# ProPrj__PCB__2026-04-20.net
KiCad netlist of a schematic drawn in EasyEDA Pro
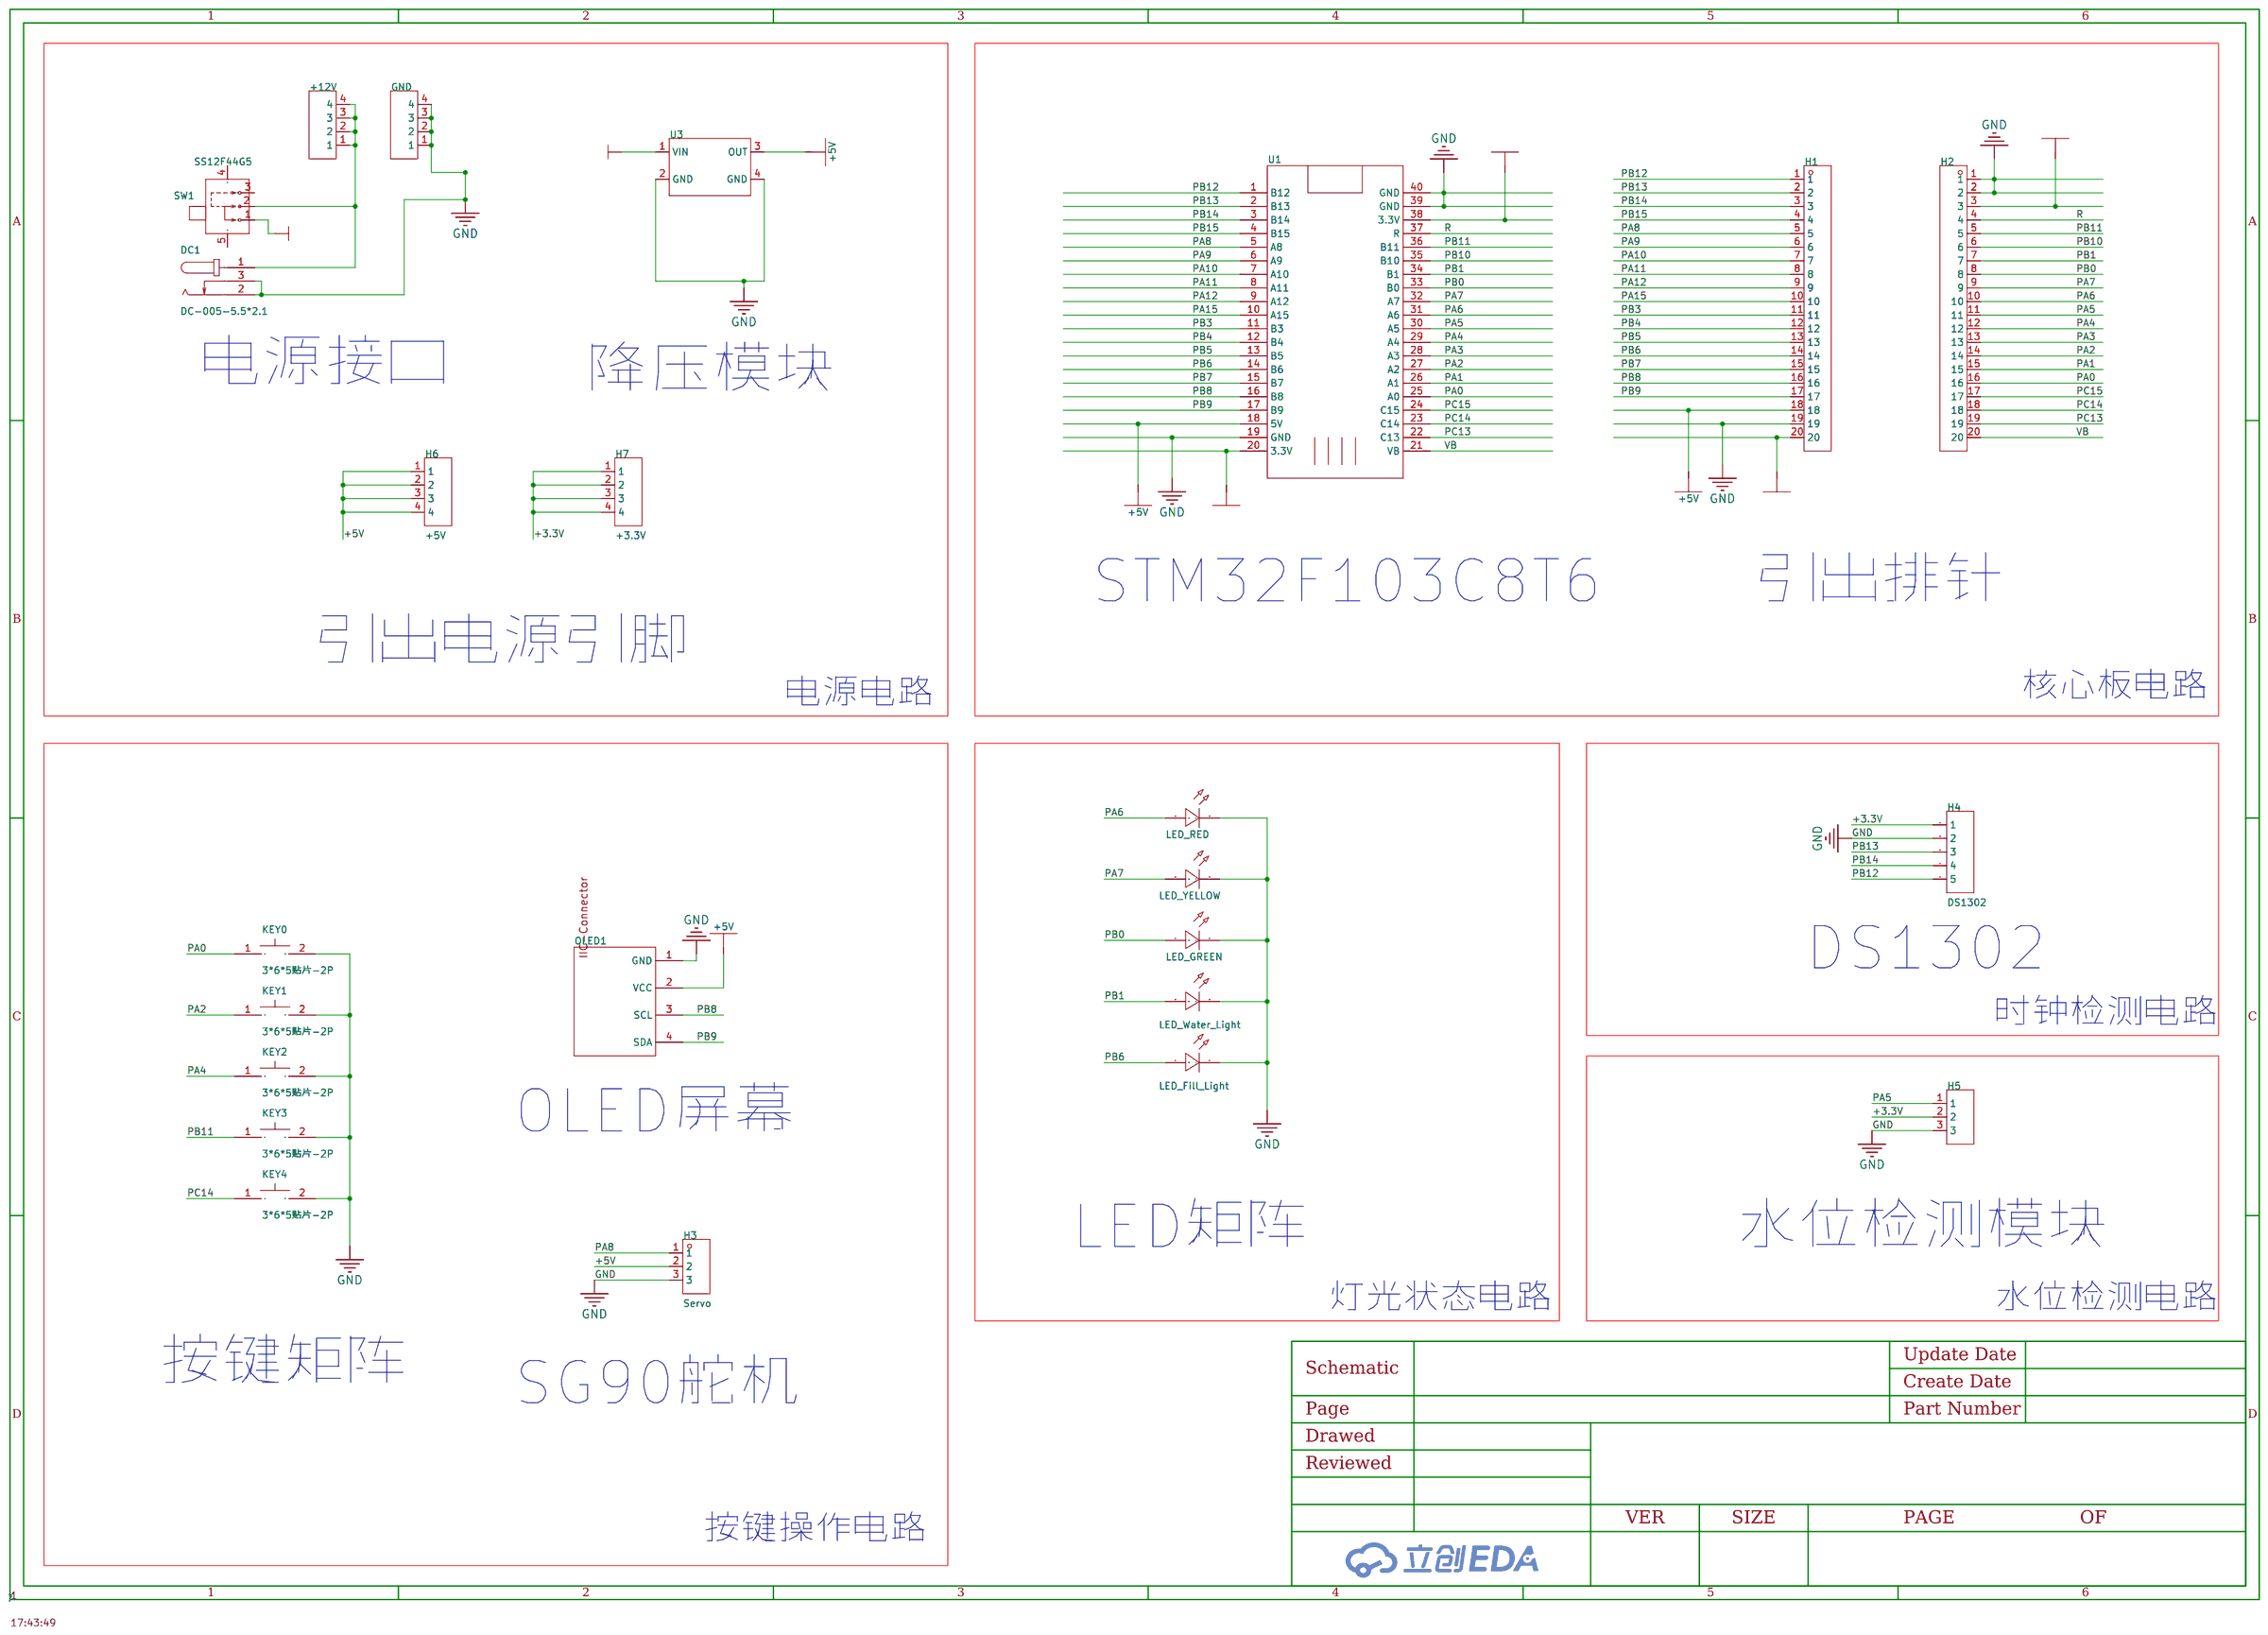
[diagram p0: schematic sheet]

(export (version "E")
  (design (tool "Eeschema 10.0.6"))
  (components
    (comp (ref "+12V")
      (value "~")
      (footprint "easyedapro:HDR-TH_4P-P2.54-V-M")
      (libsource (lib "easyedapro") (part "PZ254V-11-04P"))
    )
    (comp (ref "DC1")
      (value "DC-005-5.5*2.1")
      (footprint "easyedapro:DC-IN-TH_DC-005-2")
      (libsource (lib "easyedapro") (part "DC-005-5.5*2.1"))
    )
    (comp (ref "GND")
      (value "~")
      (footprint "easyedapro:HDR-TH_4P-P2.54-V-M")
      (libsource (lib "easyedapro") (part "PZ254V-11-04P"))
    )
    (comp (ref "H1")
      (value "~")
      (footprint "easyedapro:HDR-TH_20P-P2.54-V-M-1")
      (libsource (lib "easyedapro") (part "HDR_2.54-1x20P"))
    )
    (comp (ref "H2")
      (value "~")
      (footprint "easyedapro:HDR-TH_20P-P2.54-V-M-1")
      (libsource (lib "easyedapro") (part "HDR_2.54-1x20P"))
    )
    (comp (ref "H3")
      (value "Servo")
      (footprint "easyedapro:HDR-TH_3P-P2.54-V-M")
      (libsource (lib "easyedapro") (part "HDR-M_2.54_1x3P"))
    )
    (comp (ref "H4")
      (value "DS1302")
      (footprint "easyedapro:HDR-TH_5P-P2.54-V-F")
      (libsource (lib "easyedapro") (part "Header-Female-2.54_1x5"))
    )
    (comp (ref "H5")
      (value "~")
      (footprint "easyedapro:HDR-TH_3P-P2.54-V-F")
      (libsource (lib "easyedapro") (part "PM254V-11-03-H85"))
    )
    (comp (ref "H6")
      (value "+5V")
      (footprint "easyedapro:HDR-TH_4P-P2.54-V-M")
      (libsource (lib "easyedapro") (part "PZ254V-11-04P"))
    )
    (comp (ref "H7")
      (value "+3.3V")
      (footprint "easyedapro:HDR-TH_4P-P2.54-V-M")
      (libsource (lib "easyedapro") (part "PZ254V-11-04P"))
    )
    (comp (ref "KEY0")
      (value "3*6*5贴片-2P")
      (footprint "easyedapro:SW-SMD_L6.0-W3.5-LS8.0")
      (libsource (lib "easyedapro") (part "3*6*5贴片-2P"))
    )
    (comp (ref "KEY1")
      (value "3*6*5贴片-2P")
      (footprint "easyedapro:SW-SMD_L6.0-W3.5-LS8.0")
      (libsource (lib "easyedapro") (part "3*6*5贴片-2P"))
    )
    (comp (ref "KEY2")
      (value "3*6*5贴片-2P")
      (footprint "easyedapro:SW-SMD_L6.0-W3.5-LS8.0")
      (libsource (lib "easyedapro") (part "3*6*5贴片-2P"))
    )
    (comp (ref "KEY3")
      (value "3*6*5贴片-2P")
      (footprint "easyedapro:SW-SMD_L6.0-W3.5-LS8.0")
      (libsource (lib "easyedapro") (part "3*6*5贴片-2P"))
    )
    (comp (ref "KEY4")
      (value "3*6*5贴片-2P")
      (footprint "easyedapro:SW-SMD_L6.0-W3.5-LS8.0")
      (libsource (lib "easyedapro") (part "3*6*5贴片-2P"))
    )
    (comp (ref "LED_Fill_Light")
      (value "~")
      (footprint "easyedapro:LED_TH-_5mm")
      (libsource (lib "easyedapro") (part "LED_TH-B"))
    )
    (comp (ref "LED_GREEN")
      (value "~")
      (footprint "easyedapro:LED_TH-_5mm")
      (libsource (lib "easyedapro") (part "LED_TH-G"))
    )
    (comp (ref "LED_RED")
      (value "~")
      (footprint "easyedapro:LED_TH-_5mm")
      (libsource (lib "easyedapro") (part "LED_TH-R"))
    )
    (comp (ref "LED_Water_Light")
      (value "~")
      (footprint "easyedapro:LED_TH-_5mm")
      (libsource (lib "easyedapro") (part "LED_TH-B"))
    )
    (comp (ref "LED_YELLOW")
      (value "~")
      (footprint "easyedapro:LED_TH-_5mm")
      (libsource (lib "easyedapro") (part "LED_TH-B"))
    )
    (comp (ref "OLED1")
      (value "~")
      (fields (field (name "Manufacturer Part") "0.96OLED_4P_MODULE_JX"))
      (libsource (lib "easyedapro") (part "0.96OLED_4P_MODULE_JX"))
    )
    (comp (ref "SW1")
      (value "SS12F44G5")
      (footprint "easyedapro:SW-TH_SHOU-HAN_SS12F44G4")
      (description "拨动开关 立式直脚插件 二档 柄高5mm")
      (fields (field (name "Manufacturer") "HanElectricity(瀚源)"))
      (libsource (lib "easyedapro") (part "SS12F44G5"))
    )
    (comp (ref "U1") (value "~") (libsource (lib "easyedapro") (part "STM32F103C8T6核心板")))
    (comp (ref "U3")
      (value "~")
      (footprint "easyedapro:MP1584模块")
      (libsource (lib "easyedapro") (part "MP1584模块"))
    )
  )
  (nets
    (net (code "1") (name "+3.3V") (class "Default")
      (node (ref "H1") (pin "20") (pinfunction "20_20") (pintype "input"))
      (node (ref "H2") (pin "3") (pinfunction "3_3") (pintype "input"))
      (node (ref "H4") (pin "1") (pinfunction "1_1") (pintype "input"))
      (node (ref "H5") (pin "2") (pinfunction "2_2") (pintype "unspecified"))
      (node (ref "H7") (pin "1") (pinfunction "1_1") (pintype "unspecified"))
      (node (ref "H7") (pin "2") (pinfunction "2_2") (pintype "unspecified"))
      (node (ref "H7") (pin "3") (pinfunction "3_3") (pintype "unspecified"))
      (node (ref "H7") (pin "4") (pinfunction "4_4") (pintype "unspecified"))
      (node (ref "U1") (pin "20") (pinfunction "3.3V_20") (pintype "unspecified"))
      (node (ref "U1") (pin "38") (pinfunction "3.3V_38") (pintype "unspecified"))
    )
    (net (code "2") (name "+5V") (class "Default")
      (node (ref "H1") (pin "18") (pinfunction "18_18") (pintype "input"))
      (node (ref "H3") (pin "2") (pinfunction "2_2") (pintype "input"))
      (node (ref "H6") (pin "1") (pinfunction "1_1") (pintype "unspecified"))
      (node (ref "H6") (pin "2") (pinfunction "2_2") (pintype "unspecified"))
      (node (ref "H6") (pin "3") (pinfunction "3_3") (pintype "unspecified"))
      (node (ref "H6") (pin "4") (pinfunction "4_4") (pintype "unspecified"))
      (node (ref "OLED1") (pin "2") (pinfunction "VCC_2") (pintype "input"))
      (node (ref "U1") (pin "18") (pinfunction "5V_18") (pintype "unspecified"))
      (node (ref "U3") (pin "3") (pinfunction "OUT_3") (pintype "unspecified"))
    )
    (net (code "3") (name "+12V") (class "Default")
      (node (ref "SW1") (pin "1") (pinfunction "1_1") (pintype "unspecified"))
      (node (ref "U3") (pin "1") (pinfunction "VIN_1") (pintype "unspecified"))
    )
    (net (code "4") (name "/PA0") (class "Default")
      (node (ref "H2") (pin "16") (pinfunction "16_16") (pintype "input"))
      (node (ref "KEY0") (pin "1") (pinfunction "1_1") (pintype "unspecified"))
      (node (ref "U1") (pin "25") (pinfunction "A0_25") (pintype "unspecified"))
    )
    (net (code "5") (name "/PA1") (class "Default")
      (node (ref "H2") (pin "15") (pinfunction "15_15") (pintype "input"))
      (node (ref "U1") (pin "26") (pinfunction "A1_26") (pintype "unspecified"))
    )
    (net (code "6") (name "/PA2") (class "Default")
      (node (ref "H2") (pin "14") (pinfunction "14_14") (pintype "input"))
      (node (ref "KEY1") (pin "1") (pinfunction "1_1") (pintype "unspecified"))
      (node (ref "U1") (pin "27") (pinfunction "A2_27") (pintype "unspecified"))
    )
    (net (code "7") (name "/PA3") (class "Default")
      (node (ref "H2") (pin "13") (pinfunction "13_13") (pintype "input"))
      (node (ref "U1") (pin "28") (pinfunction "A3_28") (pintype "unspecified"))
    )
    (net (code "8") (name "/PA4") (class "Default")
      (node (ref "H2") (pin "12") (pinfunction "12_12") (pintype "input"))
      (node (ref "KEY2") (pin "1") (pinfunction "1_1") (pintype "unspecified"))
      (node (ref "U1") (pin "29") (pinfunction "A4_29") (pintype "unspecified"))
    )
    (net (code "9") (name "/PA5") (class "Default")
      (node (ref "H2") (pin "11") (pinfunction "11_11") (pintype "input"))
      (node (ref "H5") (pin "1") (pinfunction "1_1") (pintype "unspecified"))
      (node (ref "U1") (pin "30") (pinfunction "A5_30") (pintype "unspecified"))
    )
    (net (code "10") (name "/PA6") (class "Default")
      (node (ref "H2") (pin "10") (pinfunction "10_10") (pintype "input"))
      (node (ref "LED_RED") (pin "1") (pinfunction "C_1") (pintype "input"))
      (node (ref "U1") (pin "31") (pinfunction "A6_31") (pintype "unspecified"))
    )
    (net (code "11") (name "/PA7") (class "Default")
      (node (ref "H2") (pin "9") (pinfunction "9_9") (pintype "input"))
      (node (ref "LED_YELLOW") (pin "1") (pinfunction "C_1") (pintype "input"))
      (node (ref "U1") (pin "32") (pinfunction "A7_32") (pintype "unspecified"))
    )
    (net (code "12") (name "/PA8") (class "Default")
      (node (ref "H1") (pin "5") (pinfunction "5_5") (pintype "input"))
      (node (ref "H3") (pin "1") (pinfunction "1_1") (pintype "input"))
      (node (ref "U1") (pin "5") (pinfunction "A8_5") (pintype "unspecified"))
    )
    (net (code "13") (name "/PA9") (class "Default")
      (node (ref "H1") (pin "6") (pinfunction "6_6") (pintype "input"))
      (node (ref "U1") (pin "6") (pinfunction "A9_6") (pintype "unspecified"))
    )
    (net (code "14") (name "/PA10") (class "Default")
      (node (ref "H1") (pin "7") (pinfunction "7_7") (pintype "input"))
      (node (ref "U1") (pin "7") (pinfunction "A10_7") (pintype "unspecified"))
    )
    (net (code "15") (name "/PA11") (class "Default")
      (node (ref "H1") (pin "8") (pinfunction "8_8") (pintype "input"))
      (node (ref "U1") (pin "8") (pinfunction "A11_8") (pintype "unspecified"))
    )
    (net (code "16") (name "/PA12") (class "Default")
      (node (ref "H1") (pin "9") (pinfunction "9_9") (pintype "input"))
      (node (ref "U1") (pin "9") (pinfunction "A12_9") (pintype "unspecified"))
    )
    (net (code "17") (name "/PA15") (class "Default")
      (node (ref "H1") (pin "10") (pinfunction "10_10") (pintype "input"))
      (node (ref "U1") (pin "10") (pinfunction "A15_10") (pintype "unspecified"))
    )
    (net (code "18") (name "/PB0") (class "Default")
      (node (ref "H2") (pin "8") (pinfunction "8_8") (pintype "input"))
      (node (ref "LED_GREEN") (pin "1") (pinfunction "C_1") (pintype "input"))
      (node (ref "U1") (pin "33") (pinfunction "B0_33") (pintype "unspecified"))
    )
    (net (code "19") (name "/PB1") (class "Default")
      (node (ref "H2") (pin "7") (pinfunction "7_7") (pintype "input"))
      (node (ref "LED_Water_Light") (pin "1") (pinfunction "C_1") (pintype "input"))
      (node (ref "U1") (pin "34") (pinfunction "B1_34") (pintype "unspecified"))
    )
    (net (code "20") (name "/PB3") (class "Default")
      (node (ref "H1") (pin "11") (pinfunction "11_11") (pintype "input"))
      (node (ref "U1") (pin "11") (pinfunction "B3_11") (pintype "unspecified"))
    )
    (net (code "21") (name "/PB4") (class "Default")
      (node (ref "H1") (pin "12") (pinfunction "12_12") (pintype "input"))
      (node (ref "U1") (pin "12") (pinfunction "B4_12") (pintype "unspecified"))
    )
    (net (code "22") (name "/PB5") (class "Default")
      (node (ref "H1") (pin "13") (pinfunction "13_13") (pintype "input"))
      (node (ref "U1") (pin "13") (pinfunction "B5_13") (pintype "unspecified"))
    )
    (net (code "23") (name "/PB6") (class "Default")
      (node (ref "H1") (pin "14") (pinfunction "14_14") (pintype "input"))
      (node (ref "LED_Fill_Light") (pin "1") (pinfunction "C_1") (pintype "input"))
      (node (ref "U1") (pin "14") (pinfunction "B6_14") (pintype "unspecified"))
    )
    (net (code "24") (name "/PB7") (class "Default")
      (node (ref "H1") (pin "15") (pinfunction "15_15") (pintype "input"))
      (node (ref "U1") (pin "15") (pinfunction "B7_15") (pintype "unspecified"))
    )
    (net (code "25") (name "/PB8") (class "Default")
      (node (ref "H1") (pin "16") (pinfunction "16_16") (pintype "input"))
      (node (ref "OLED1") (pin "3") (pinfunction "SCL_3") (pintype "input"))
      (node (ref "U1") (pin "16") (pinfunction "B8_16") (pintype "unspecified"))
    )
    (net (code "26") (name "/PB9") (class "Default")
      (node (ref "H1") (pin "17") (pinfunction "17_17") (pintype "input"))
      (node (ref "OLED1") (pin "4") (pinfunction "SDA_4") (pintype "input"))
      (node (ref "U1") (pin "17") (pinfunction "B9_17") (pintype "unspecified"))
    )
    (net (code "27") (name "/PB10") (class "Default")
      (node (ref "H2") (pin "6") (pinfunction "6_6") (pintype "input"))
      (node (ref "U1") (pin "35") (pinfunction "B10_35") (pintype "unspecified"))
    )
    (net (code "28") (name "/PB11") (class "Default")
      (node (ref "H2") (pin "5") (pinfunction "5_5") (pintype "input"))
      (node (ref "KEY3") (pin "1") (pinfunction "1_1") (pintype "unspecified"))
      (node (ref "U1") (pin "36") (pinfunction "B11_36") (pintype "unspecified"))
    )
    (net (code "29") (name "/PB12") (class "Default")
      (node (ref "H1") (pin "1") (pinfunction "1_1") (pintype "input"))
      (node (ref "H4") (pin "5") (pinfunction "5_5") (pintype "input"))
      (node (ref "U1") (pin "1") (pinfunction "B12_1") (pintype "unspecified"))
    )
    (net (code "30") (name "/PB13") (class "Default")
      (node (ref "H1") (pin "2") (pinfunction "2_2") (pintype "input"))
      (node (ref "H4") (pin "3") (pinfunction "3_3") (pintype "input"))
      (node (ref "U1") (pin "2") (pinfunction "B13_2") (pintype "unspecified"))
    )
    (net (code "31") (name "/PB14") (class "Default")
      (node (ref "H1") (pin "3") (pinfunction "3_3") (pintype "input"))
      (node (ref "H4") (pin "4") (pinfunction "4_4") (pintype "input"))
      (node (ref "U1") (pin "3") (pinfunction "B14_3") (pintype "unspecified"))
    )
    (net (code "32") (name "/PB15") (class "Default")
      (node (ref "H1") (pin "4") (pinfunction "4_4") (pintype "input"))
      (node (ref "U1") (pin "4") (pinfunction "B15_4") (pintype "unspecified"))
    )
    (net (code "33") (name "/PC13") (class "Default")
      (node (ref "H2") (pin "19") (pinfunction "19_19") (pintype "input"))
      (node (ref "U1") (pin "22") (pinfunction "C13_22") (pintype "unspecified"))
    )
    (net (code "34") (name "/PC14") (class "Default")
      (node (ref "H2") (pin "18") (pinfunction "18_18") (pintype "input"))
      (node (ref "KEY4") (pin "1") (pinfunction "1_1") (pintype "unspecified"))
      (node (ref "U1") (pin "23") (pinfunction "C14_23") (pintype "unspecified"))
    )
    (net (code "35") (name "/PC15") (class "Default")
      (node (ref "H2") (pin "17") (pinfunction "17_17") (pintype "input"))
      (node (ref "U1") (pin "24") (pinfunction "C15_24") (pintype "unspecified"))
    )
    (net (code "36") (name "/R") (class "Default")
      (node (ref "H2") (pin "4") (pinfunction "4_4") (pintype "input"))
      (node (ref "U1") (pin "37") (pinfunction "R_37") (pintype "unspecified"))
    )
    (net (code "37") (name "/VB") (class "Default")
      (node (ref "H2") (pin "20") (pinfunction "20_20") (pintype "input"))
      (node (ref "U1") (pin "21") (pinfunction "VB_21") (pintype "unspecified"))
    )
    (net (code "38") (name "GND") (class "Default")
      (node (ref "DC1") (pin "2") (pinfunction "2_2") (pintype "unspecified"))
      (node (ref "DC1") (pin "3") (pinfunction "3_3") (pintype "unspecified"))
      (node (ref "GND") (pin "1") (pinfunction "1_1") (pintype "unspecified"))
      (node (ref "GND") (pin "2") (pinfunction "2_2") (pintype "unspecified"))
      (node (ref "GND") (pin "3") (pinfunction "3_3") (pintype "unspecified"))
      (node (ref "GND") (pin "4") (pinfunction "4_4") (pintype "unspecified"))
      (node (ref "H1") (pin "19") (pinfunction "19_19") (pintype "input"))
      (node (ref "H2") (pin "1") (pinfunction "1_1") (pintype "input"))
      (node (ref "H2") (pin "2") (pinfunction "2_2") (pintype "input"))
      (node (ref "H3") (pin "3") (pinfunction "3_3") (pintype "input"))
      (node (ref "H4") (pin "2") (pinfunction "2_2") (pintype "input"))
      (node (ref "H5") (pin "3") (pinfunction "3_3") (pintype "unspecified"))
      (node (ref "KEY0") (pin "2") (pinfunction "2_2") (pintype "unspecified"))
      (node (ref "KEY1") (pin "2") (pinfunction "2_2") (pintype "unspecified"))
      (node (ref "KEY2") (pin "2") (pinfunction "2_2") (pintype "unspecified"))
      (node (ref "KEY3") (pin "2") (pinfunction "2_2") (pintype "unspecified"))
      (node (ref "KEY4") (pin "2") (pinfunction "2_2") (pintype "unspecified"))
      (node (ref "LED_Fill_Light") (pin "2") (pinfunction "A_2") (pintype "input"))
      (node (ref "LED_GREEN") (pin "2") (pinfunction "A_2") (pintype "input"))
      (node (ref "LED_RED") (pin "2") (pinfunction "A_2") (pintype "input"))
      (node (ref "LED_Water_Light") (pin "2") (pinfunction "A_2") (pintype "input"))
      (node (ref "LED_YELLOW") (pin "2") (pinfunction "A_2") (pintype "input"))
      (node (ref "OLED1") (pin "1") (pinfunction "GND_1") (pintype "input"))
      (node (ref "U1") (pin "19") (pinfunction "GND_19") (pintype "unspecified"))
      (node (ref "U1") (pin "39") (pinfunction "GND_39") (pintype "unspecified"))
      (node (ref "U1") (pin "40") (pinfunction "GND_40") (pintype "unspecified"))
      (node (ref "U3") (pin "2") (pinfunction "GND_2") (pintype "unspecified"))
      (node (ref "U3") (pin "4") (pinfunction "GND_4") (pintype "unspecified"))
    )
    (net (code "39") (name "Net-(+12V-Pad1)") (class "Default")
      (node (ref "+12V") (pin "1") (pinfunction "1_1") (pintype "unspecified"))
      (node (ref "+12V") (pin "2") (pinfunction "2_2") (pintype "unspecified"))
      (node (ref "+12V") (pin "3") (pinfunction "3_3") (pintype "unspecified"))
      (node (ref "+12V") (pin "4") (pinfunction "4_4") (pintype "unspecified"))
      (node (ref "DC1") (pin "1") (pinfunction "1_1") (pintype "unspecified"))
      (node (ref "SW1") (pin "2") (pinfunction "2_2") (pintype "unspecified"))
    )
    (net (code "40") (name "unconnected-(SW1-Pad3)") (class "Default")
      (node (ref "SW1") (pin "3") (pinfunction "3_3") (pintype "unspecified"))
    )
    (net (code "41") (name "unconnected-(SW1-Pad4)") (class "Default")
      (node (ref "SW1") (pin "4") (pinfunction "4_4") (pintype "unspecified"))
    )
    (net (code "42") (name "unconnected-(SW1-Pad5)") (class "Default")
      (node (ref "SW1") (pin "5") (pinfunction "5_5") (pintype "unspecified"))
    )
  )
)
